# SCH_fightpad_2024-06-17_1.net
KiCad netlist of a schematic drawn in EasyEDA
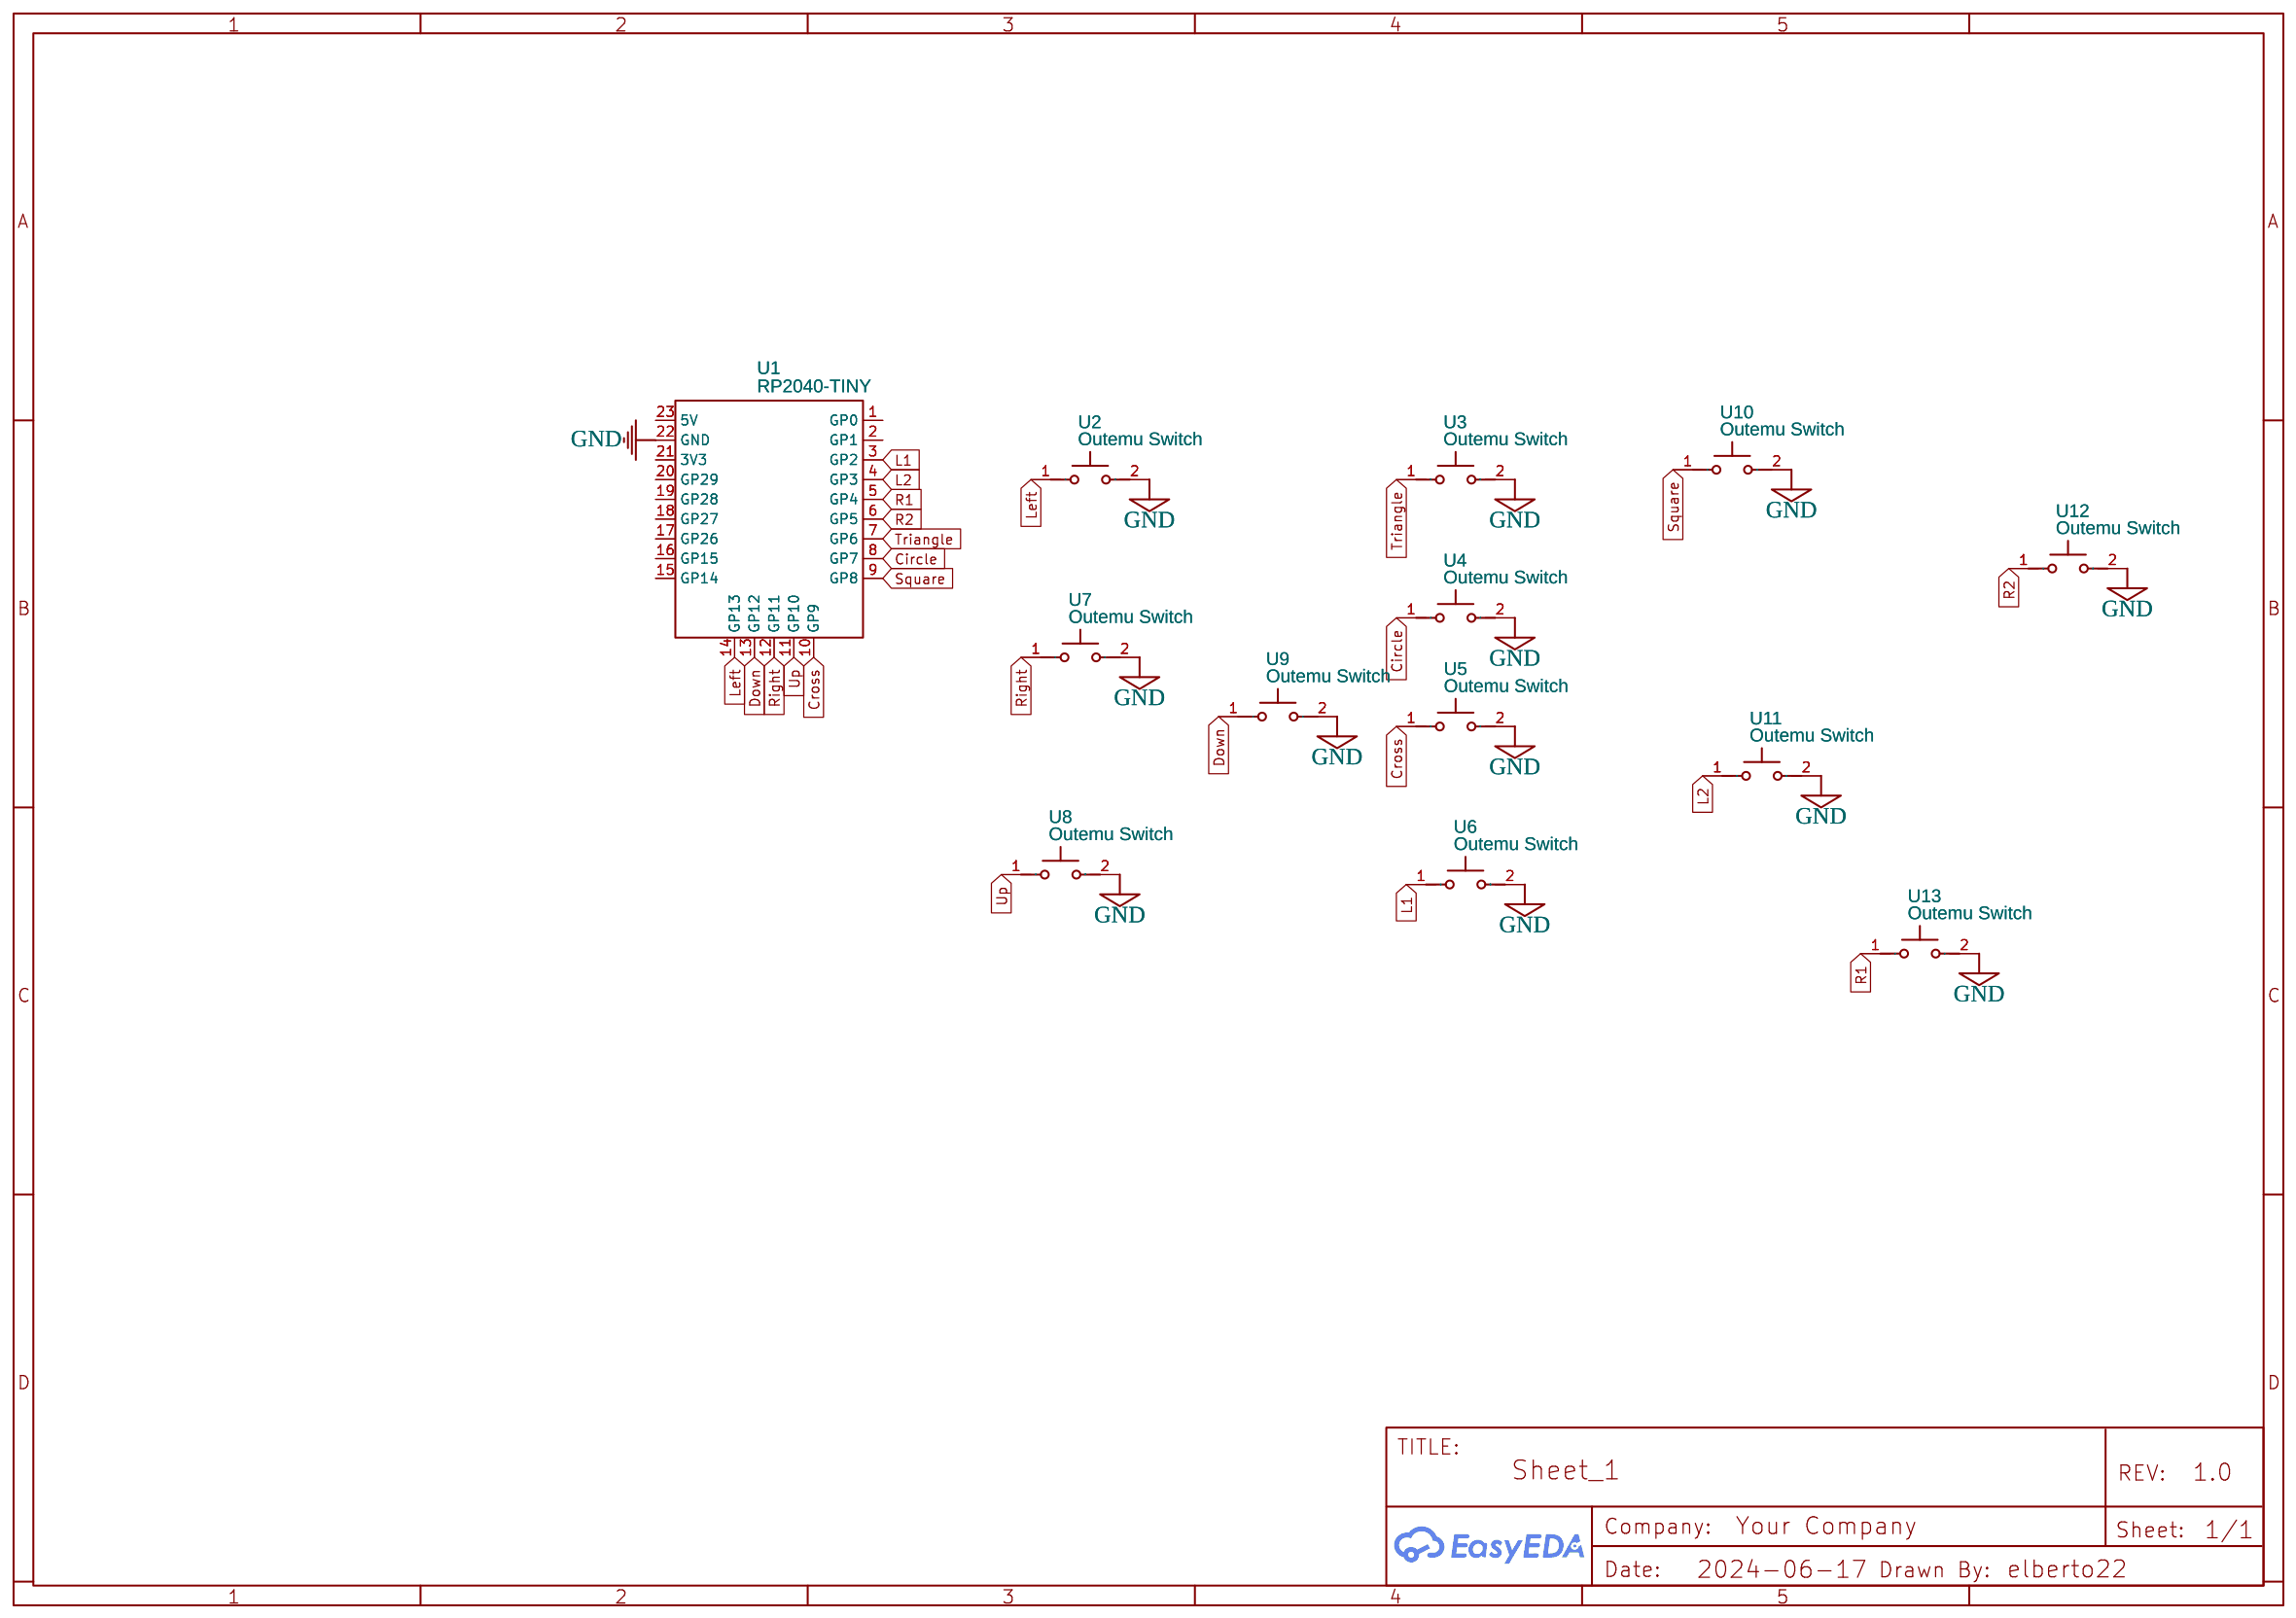
[diagram p0: schematic sheet]

(export (version "E")
  (design (tool "Eeschema 10.0.6"))
  (components
    (comp (ref "U1")
      (value "RP2040-TINY")
      (fields
        (field (name "Manufacturer Part") "RP2040-Tiny")
        (field (name "Manufacturer") "Waveshare(微雪电子)")
      )
      (libsource (lib "") (part "RP2040-TINY"))
    )
    (comp (ref "U2")
      (value "Outemu Switch")
      (fields (field (name "Manufacturer") "HepLer"))
      (libsource (lib "") (part "Outemu Switch"))
    )
    (comp (ref "U3")
      (value "Outemu Switch")
      (fields (field (name "Manufacturer") "HepLer"))
      (libsource (lib "") (part "Outemu Switch"))
    )
    (comp (ref "U4")
      (value "Outemu Switch")
      (fields (field (name "Manufacturer") "HepLer"))
      (libsource (lib "") (part "Outemu Switch"))
    )
    (comp (ref "U5")
      (value "Outemu Switch")
      (fields (field (name "Manufacturer") "HepLer"))
      (libsource (lib "") (part "Outemu Switch"))
    )
    (comp (ref "U6")
      (value "Outemu Switch")
      (fields (field (name "Manufacturer") "HepLer"))
      (libsource (lib "") (part "Outemu Switch"))
    )
    (comp (ref "U7")
      (value "Outemu Switch")
      (fields (field (name "Manufacturer") "HepLer"))
      (libsource (lib "") (part "Outemu Switch"))
    )
    (comp (ref "U8")
      (value "Outemu Switch")
      (fields (field (name "Manufacturer") "HepLer"))
      (libsource (lib "") (part "Outemu Switch"))
    )
    (comp (ref "U9")
      (value "Outemu Switch")
      (fields (field (name "Manufacturer") "HepLer"))
      (libsource (lib "") (part "Outemu Switch"))
    )
    (comp (ref "U10")
      (value "Outemu Switch")
      (fields (field (name "Manufacturer") "HepLer"))
      (libsource (lib "") (part "Outemu Switch"))
    )
    (comp (ref "U11")
      (value "Outemu Switch")
      (fields (field (name "Manufacturer") "HepLer"))
      (libsource (lib "") (part "Outemu Switch"))
    )
    (comp (ref "U12")
      (value "Outemu Switch")
      (fields (field (name "Manufacturer") "HepLer"))
      (libsource (lib "") (part "Outemu Switch"))
    )
    (comp (ref "U13")
      (value "Outemu Switch")
      (fields (field (name "Manufacturer") "HepLer"))
      (libsource (lib "") (part "Outemu Switch"))
    )
  )
  (nets
    (net (code "1") (name "Circle") (class "Default")
      (node (ref "U1") (pin "8") (pinfunction "GP7_8") (pintype "unspecified"))
      (node (ref "U4") (pin "1") (pinfunction "1_1") (pintype "unspecified"))
    )
    (net (code "2") (name "Cross") (class "Default")
      (node (ref "U1") (pin "10") (pinfunction "GP9_10") (pintype "unspecified"))
      (node (ref "U5") (pin "1") (pinfunction "1_1") (pintype "unspecified"))
    )
    (net (code "3") (name "Down") (class "Default")
      (node (ref "U1") (pin "13") (pinfunction "GP12_13") (pintype "unspecified"))
      (node (ref "U9") (pin "1") (pinfunction "1_1") (pintype "unspecified"))
    )
    (net (code "4") (name "GND") (class "Default")
      (node (ref "U1") (pin "22") (pinfunction "GND_22") (pintype "unspecified"))
      (node (ref "U10") (pin "2") (pinfunction "2_2") (pintype "unspecified"))
      (node (ref "U11") (pin "2") (pinfunction "2_2") (pintype "unspecified"))
      (node (ref "U12") (pin "2") (pinfunction "2_2") (pintype "unspecified"))
      (node (ref "U13") (pin "2") (pinfunction "2_2") (pintype "unspecified"))
      (node (ref "U2") (pin "2") (pinfunction "2_2") (pintype "unspecified"))
      (node (ref "U3") (pin "2") (pinfunction "2_2") (pintype "unspecified"))
      (node (ref "U4") (pin "2") (pinfunction "2_2") (pintype "unspecified"))
      (node (ref "U5") (pin "2") (pinfunction "2_2") (pintype "unspecified"))
      (node (ref "U6") (pin "2") (pinfunction "2_2") (pintype "unspecified"))
      (node (ref "U7") (pin "2") (pinfunction "2_2") (pintype "unspecified"))
      (node (ref "U8") (pin "2") (pinfunction "2_2") (pintype "unspecified"))
      (node (ref "U9") (pin "2") (pinfunction "2_2") (pintype "unspecified"))
    )
    (net (code "5") (name "L1") (class "Default")
      (node (ref "U1") (pin "3") (pinfunction "GP2_3") (pintype "unspecified"))
      (node (ref "U6") (pin "1") (pinfunction "1_1") (pintype "unspecified"))
    )
    (net (code "6") (name "L2") (class "Default")
      (node (ref "U1") (pin "4") (pinfunction "GP3_4") (pintype "unspecified"))
      (node (ref "U11") (pin "1") (pinfunction "1_1") (pintype "unspecified"))
    )
    (net (code "7") (name "Left") (class "Default")
      (node (ref "U1") (pin "14") (pinfunction "GP13_14") (pintype "unspecified"))
      (node (ref "U2") (pin "1") (pinfunction "1_1") (pintype "unspecified"))
    )
    (net (code "8") (name "R1") (class "Default")
      (node (ref "U1") (pin "5") (pinfunction "GP4_5") (pintype "unspecified"))
      (node (ref "U13") (pin "1") (pinfunction "1_1") (pintype "unspecified"))
    )
    (net (code "9") (name "R2") (class "Default")
      (node (ref "U1") (pin "6") (pinfunction "GP5_6") (pintype "unspecified"))
      (node (ref "U12") (pin "1") (pinfunction "1_1") (pintype "unspecified"))
    )
    (net (code "10") (name "Right") (class "Default")
      (node (ref "U1") (pin "12") (pinfunction "GP11_12") (pintype "unspecified"))
      (node (ref "U7") (pin "1") (pinfunction "1_1") (pintype "unspecified"))
    )
    (net (code "11") (name "Square") (class "Default")
      (node (ref "U1") (pin "9") (pinfunction "GP8_9") (pintype "unspecified"))
      (node (ref "U10") (pin "1") (pinfunction "1_1") (pintype "unspecified"))
    )
    (net (code "12") (name "Triangle") (class "Default")
      (node (ref "U1") (pin "7") (pinfunction "GP6_7") (pintype "unspecified"))
      (node (ref "U3") (pin "1") (pinfunction "1_1") (pintype "unspecified"))
    )
    (net (code "13") (name "Up") (class "Default")
      (node (ref "U1") (pin "11") (pinfunction "GP10_11") (pintype "unspecified"))
      (node (ref "U8") (pin "1") (pinfunction "1_1") (pintype "unspecified"))
    )
    (net (code "14") (name "unconnected-(U1-3V3-Pad21)") (class "Default")
      (node (ref "U1") (pin "21") (pinfunction "3V3_21") (pintype "unspecified"))
    )
    (net (code "15") (name "unconnected-(U1-5V-Pad23)") (class "Default")
      (node (ref "U1") (pin "23") (pinfunction "5V_23") (pintype "unspecified"))
    )
    (net (code "16") (name "unconnected-(U1-GP0-Pad1)") (class "Default")
      (node (ref "U1") (pin "1") (pinfunction "GP0_1") (pintype "unspecified"))
    )
    (net (code "17") (name "unconnected-(U1-GP1-Pad2)") (class "Default")
      (node (ref "U1") (pin "2") (pinfunction "GP1_2") (pintype "unspecified"))
    )
    (net (code "18") (name "unconnected-(U1-GP14-Pad15)") (class "Default")
      (node (ref "U1") (pin "15") (pinfunction "GP14_15") (pintype "unspecified"))
    )
    (net (code "19") (name "unconnected-(U1-GP15-Pad16)") (class "Default")
      (node (ref "U1") (pin "16") (pinfunction "GP15_16") (pintype "unspecified"))
    )
    (net (code "20") (name "unconnected-(U1-GP26-Pad17)") (class "Default")
      (node (ref "U1") (pin "17") (pinfunction "GP26_17") (pintype "unspecified"))
    )
    (net (code "21") (name "unconnected-(U1-GP27-Pad18)") (class "Default")
      (node (ref "U1") (pin "18") (pinfunction "GP27_18") (pintype "unspecified"))
    )
    (net (code "22") (name "unconnected-(U1-GP28-Pad19)") (class "Default")
      (node (ref "U1") (pin "19") (pinfunction "GP28_19") (pintype "unspecified"))
    )
    (net (code "23") (name "unconnected-(U1-GP29-Pad20)") (class "Default")
      (node (ref "U1") (pin "20") (pinfunction "GP29_20") (pintype "unspecified"))
    )
  )
)
